# PV_Relay.net
KiCad netlist of a schematic drawn in Altium Designer
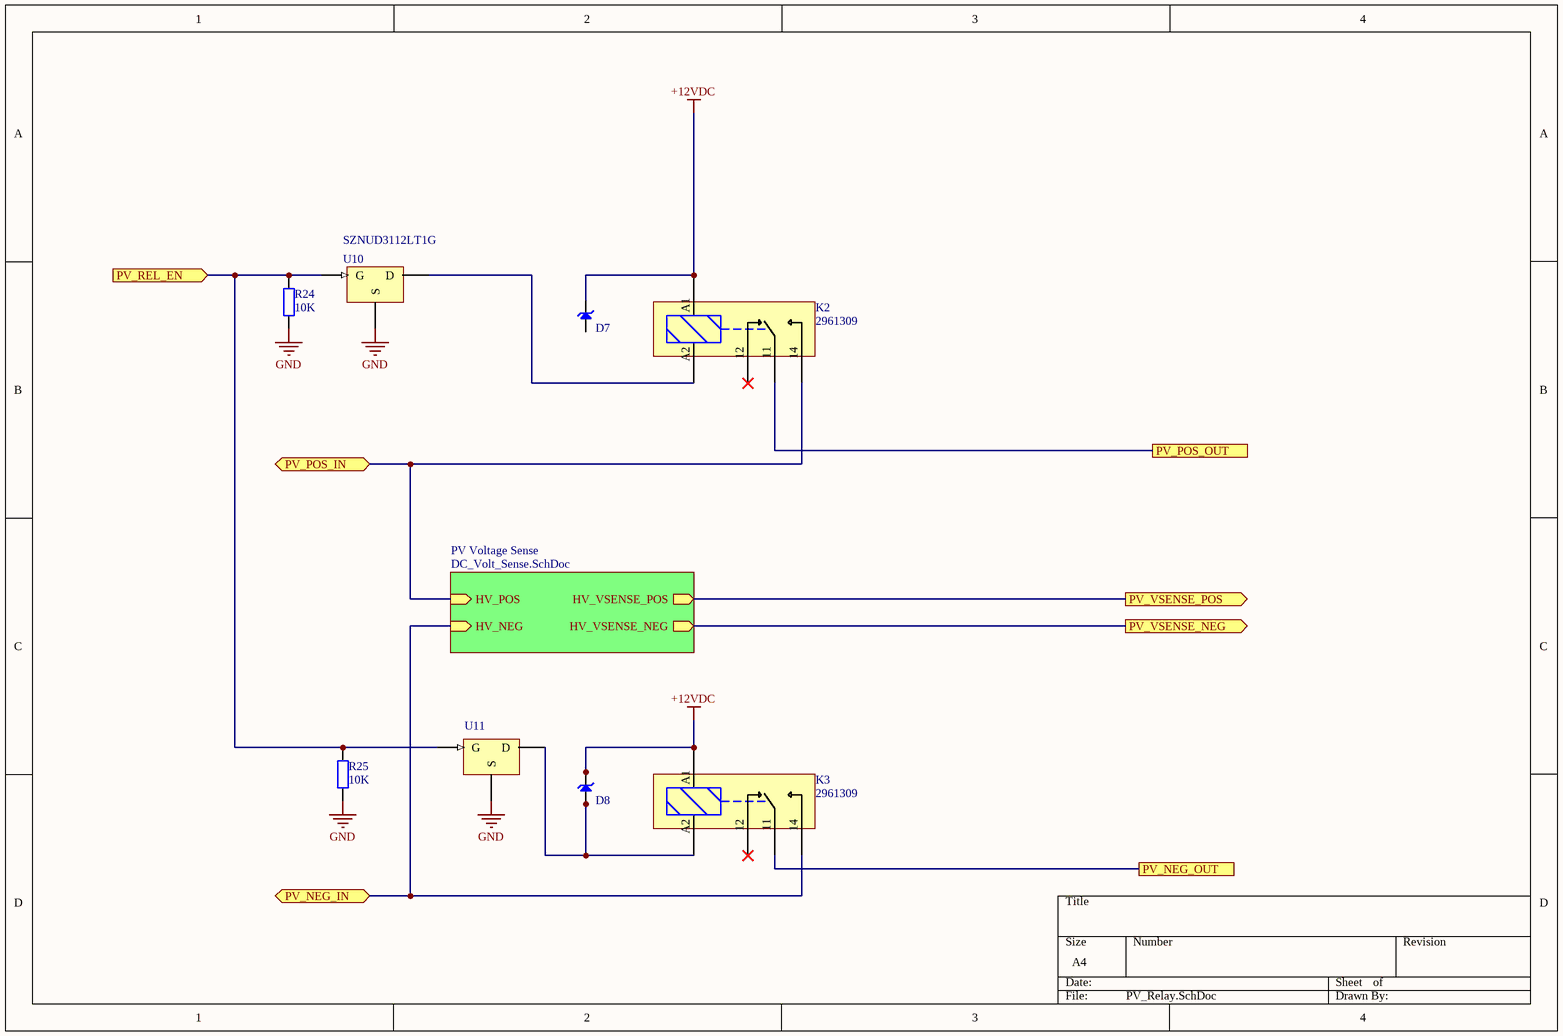
[diagram p0: PV_Relay.SchDoc]

(export (version "E")
  (design (tool "Eeschema 10.0.6"))
  (components
    (comp (ref "D7")
      (value "SMF16A")
      (footprint "SOD-123H")
      (description "Zener Diode")
      (fields (field (name "VOLTAGE") "16V") (field (name "MANUFACTURER") "Littelfuse Inc."))
      (libsource (lib "Database_library") (part "Zener_Diode"))
    )
    (comp (ref "D8")
      (value "SMF16A")
      (footprint "SOD-123H")
      (description "Zener Diode")
      (fields (field (name "VOLTAGE") "16V") (field (name "MANUFACTURER") "Littelfuse Inc."))
      (libsource (lib "Database_library") (part "Zener_Diode"))
    )
    (comp (ref "K2") (value "2961309") (footprint "2961309") (libsource (lib "Schematic") (part "2961309")))
    (comp (ref "K3") (value "2961309") (footprint "2961309") (libsource (lib "Schematic") (part "2961309")))
    (comp (ref "R24")
      (value "10K")
      (footprint "RES 0603/1608")
      (description "RES SMD 10K OHM 1% 1/10W 0603")
      (fields (field (name "PART NUMBER") "RC0603FR-0710KL") (field (name "TOLERANCE") "±1%"))
      (libsource (lib "electric_racing_lib") (part "Resistor"))
    )
    (comp (ref "R25")
      (value "10K")
      (footprint "RES 0603/1608")
      (description "RES SMD 10K OHM 1% 1/10W 0603")
      (fields (field (name "PART NUMBER") "RC0603FR-0710KL") (field (name "TOLERANCE") "±1%"))
      (libsource (lib "electric_racing_lib") (part "Resistor"))
    )
    (comp (ref "U10")
      (value "SZNUD3112LT1G")
      (footprint "SZNUD3112LT1G")
      (fields
        (field (name "PARTNUMBER") "SZNUD3112LT1GOSCT-ND")
        (field (name "MANUFACTURER") "ON Semiconductor")
      )
      (libsource (lib "Database_library") (part "SZNUD3112LT1G"))
    )
    (comp (ref "U11")
      (value "SZNUD3112LT1G")
      (footprint "SZNUD3112LT1G")
      (fields
        (field (name "PARTNUMBER") "SZNUD3112LT1GOSCT-ND")
        (field (name "MANUFACTURER") "ON Semiconductor")
      )
      (libsource (lib "Database_library") (part "SZNUD3112LT1G"))
    )
  )
  (nets
    (net (code "1") (name "+12VDC") (class "Default")
      (node (ref "D7") (pin "K") (pinfunction "K_K") (pintype "passive"))
      (node (ref "D8") (pin "K") (pinfunction "K_K") (pintype "passive"))
      (node (ref "K2") (pin "A1") (pinfunction "1_A1") (pintype "passive"))
      (node (ref "K3") (pin "A1") (pinfunction "1_A1") (pintype "passive"))
    )
    (net (code "2") (name "/PV_NEG_IN") (class "Default")
      (node (ref "K3") (pin "14") (pinfunction "14_14") (pintype "passive"))
    )
    (net (code "3") (name "/PV_NEG_OUT") (class "Default")
      (node (ref "K3") (pin "11") (pinfunction "15_11") (pintype "passive"))
    )
    (net (code "4") (name "/PV_POS_IN") (class "Default")
      (node (ref "K2") (pin "14") (pinfunction "14_14") (pintype "passive"))
    )
    (net (code "5") (name "/PV_POS_OUT") (class "Default")
      (node (ref "K2") (pin "11") (pinfunction "15_11") (pintype "passive"))
    )
    (net (code "6") (name "/PV_REL_EN") (class "Default")
      (node (ref "R24") (pin "2") (pinfunction "2_2") (pintype "passive"))
      (node (ref "R25") (pin "2") (pinfunction "2_2") (pintype "passive"))
      (node (ref "U10") (pin "1") (pinfunction "G_1") (pintype "input"))
      (node (ref "U11") (pin "1") (pinfunction "G_1") (pintype "input"))
    )
    (net (code "9") (name "GND") (class "Default")
      (node (ref "R24") (pin "1") (pinfunction "1_1") (pintype "passive"))
      (node (ref "R25") (pin "1") (pinfunction "1_1") (pintype "passive"))
      (node (ref "U10") (pin "2") (pinfunction "S_2") (pintype "passive"))
      (node (ref "U11") (pin "2") (pinfunction "S_2") (pintype "passive"))
    )
    (net (code "10") (name "Net-(K2-2)") (class "Default")
      (node (ref "K2") (pin "A2") (pinfunction "2_A2") (pintype "passive"))
      (node (ref "U10") (pin "3") (pinfunction "D_3") (pintype "passive"))
    )
    (net (code "11") (name "Net-(K3-2)") (class "Default")
      (node (ref "D8") (pin "A") (pinfunction "A_A") (pintype "passive"))
      (node (ref "K3") (pin "A2") (pinfunction "2_A2") (pintype "passive"))
      (node (ref "U11") (pin "3") (pinfunction "D_3") (pintype "passive"))
    )
    (net (code "12") (name "unconnected-(D7-PadA)") (class "Default")
      (node (ref "D7") (pin "A") (pinfunction "A_A") (pintype "passive"))
    )
    (net (code "13") (name "unconnected-(K2-16-Pad12)") (class "Default")
      (node (ref "K2") (pin "12") (pinfunction "16_12") (pintype "passive+no_connect"))
    )
    (net (code "14") (name "unconnected-(K3-16-Pad12)") (class "Default")
      (node (ref "K3") (pin "12") (pinfunction "16_12") (pintype "passive+no_connect"))
    )
  )
)
